# Camera.net
KiCad netlist of a schematic drawn in Altium Designer
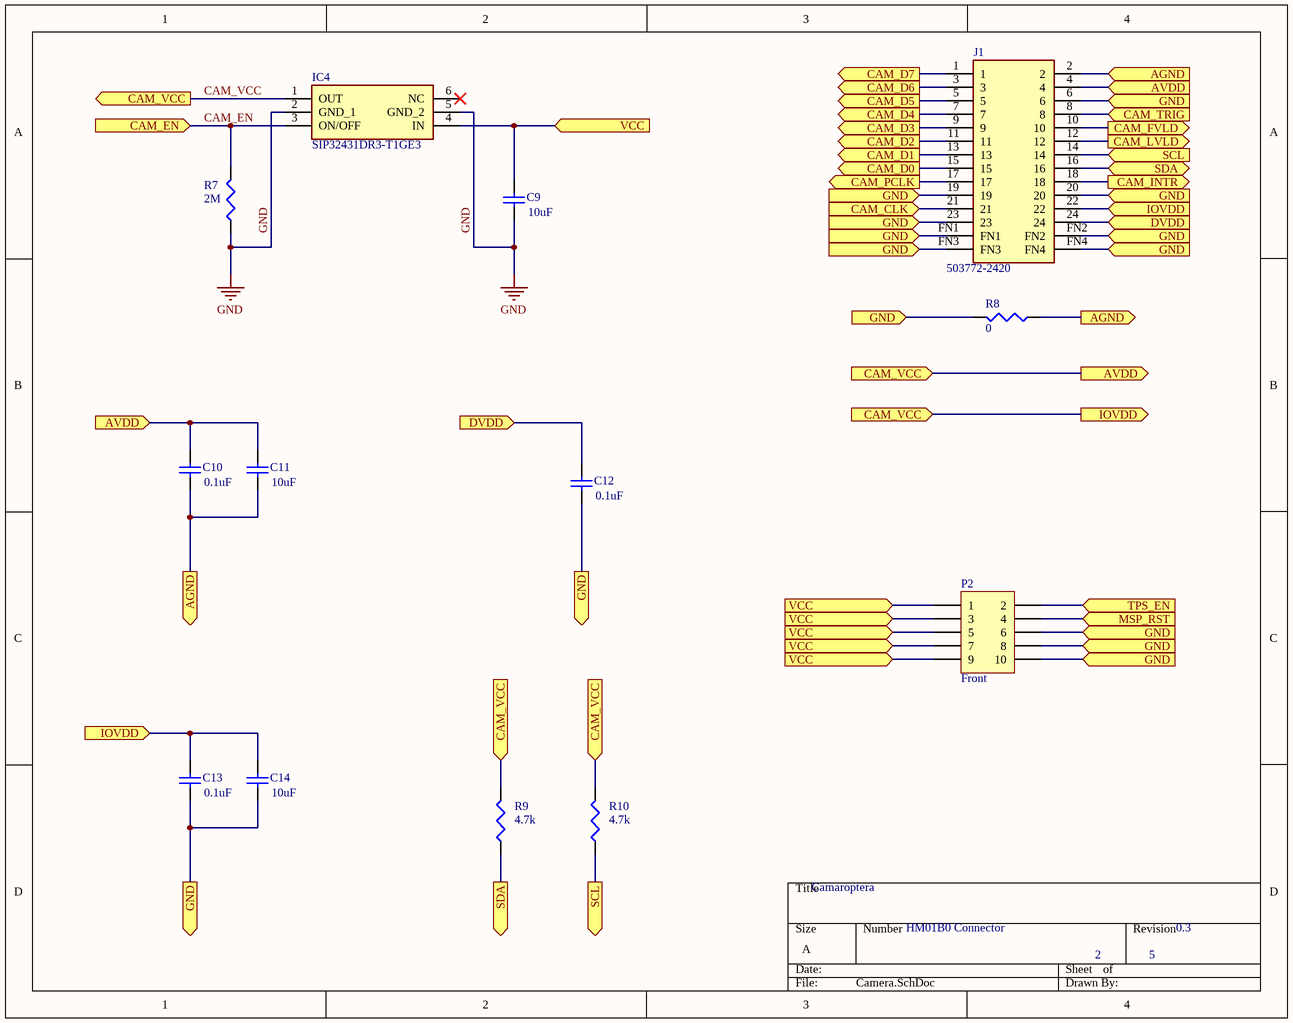
[diagram p0: Camera.SchDoc]

(export (version "E")
  (design (tool "Eeschema 10.0.6"))
  (components
    (comp (ref "C9")
      (value "10uF")
      (footprint "1608[0603]")
      (description "CAP CER 6.3V X5R/X7R 0603")
      (fields (field (name "Comment") "Cap") (field (name "PUBLISHER") "Altium Limited"))
      (libsource (lib "Miscellaneous Devices") (part "Cap"))
    )
    (comp (ref "C10")
      (value "0.1uF")
      (footprint "1608[0603]")
      (description "CAP CER 6.3V X5R/X7R 0603")
      (fields (field (name "Comment") "Cap") (field (name "PUBLISHER") "Altium Limited"))
      (libsource (lib "Miscellaneous Devices") (part "Cap"))
    )
    (comp (ref "C11")
      (value "10uF")
      (footprint "1608[0603]")
      (description "CAP CER 6.3V X5R/X7R 0603")
      (fields (field (name "Comment") "Cap") (field (name "PUBLISHER") "Altium Limited"))
      (libsource (lib "Miscellaneous Devices") (part "Cap"))
    )
    (comp (ref "C12")
      (value "0.1uF")
      (footprint "1608[0603]")
      (description "CAP CER 6.3V X5R/X7R 0603")
      (fields (field (name "Comment") "Cap") (field (name "PUBLISHER") "Altium Limited"))
      (libsource (lib "Miscellaneous Devices") (part "Cap"))
    )
    (comp (ref "C13")
      (value "0.1uF")
      (footprint "1608[0603]")
      (description "CAP CER 6.3V X5R/X7R 0603")
      (fields (field (name "Comment") "Cap") (field (name "PUBLISHER") "Altium Limited"))
      (libsource (lib "Miscellaneous Devices") (part "Cap"))
    )
    (comp (ref "C14")
      (value "10uF")
      (footprint "1608[0603]")
      (description "CAP CER 6.3V X5R/X7R 0603")
      (fields (field (name "Comment") "Cap") (field (name "PUBLISHER") "Altium Limited"))
      (libsource (lib "Miscellaneous Devices") (part "Cap"))
    )
    (comp (ref "IC4")
      (value "SIP32431DR3-T1GE3")
      (footprint "SamacSys:SOT65P210X110-6N")
      (description "10 pA, Ultra Low Leakage and Quiescent Current,\r\nLoad Switch with Reverse Blocking")
      (fields (field (name "MOUSER PART NUMBER") "781-SIP32431DR3-GE3"))
      (libsource (lib "*") (part "SIP32431DR3-T1GE3"))
    )
    (comp (ref "J1")
      (value "503772-2420")
      (footprint "SamacSys:5037722410")
      (fields
        (field (name "MOUSER PART NUMBER") "538-503772-2410")
        (field (name "MANUFACTURER_PART_NUMBER") "503772-2410")
      )
      (libsource (lib "*") (part "503772-2410"))
    )
    (comp (ref "P2")
      (value "Front")
      (footprint "FTE-105-03-X-DH")
      (description "Front  board connector")
      (fields (field (name "PUBLISHER") "Altium Limited"))
      (libsource (lib "Miscellaneous Connectors") (part "Header 5X2"))
    )
    (comp (ref "R7")
      (value "2M")
      (footprint "J1-0603")
      (description "RES 1/10W 1% 0603 SMD")
      (fields (field (name "Comment") "Res3") (field (name "PUBLISHER") "Altium Limited"))
      (libsource (lib "Miscellaneous Devices") (part "Res3"))
    )
    (comp (ref "R8")
      (value "0")
      (footprint "J1-0603")
      (description "RES 1/10W 1% 0603 SMD")
      (fields (field (name "Comment") "Res3") (field (name "PUBLISHER") "Altium Limited"))
      (libsource (lib "Miscellaneous Devices") (part "Res3"))
    )
    (comp (ref "R9")
      (value "4.7k")
      (footprint "J1-0603")
      (description "RES 1/10W 1% 0603 SMD")
      (fields (field (name "Comment") "Res3") (field (name "PUBLISHER") "Altium Limited"))
      (libsource (lib "Miscellaneous Devices") (part "Res3"))
    )
    (comp (ref "R10")
      (value "4.7k")
      (footprint "J1-0603")
      (description "RES 1/10W 1% 0603 SMD")
      (fields (field (name "Comment") "Res3") (field (name "PUBLISHER") "Altium Limited"))
      (libsource (lib "Miscellaneous Devices") (part "Res3"))
    )
  )
  (nets
    (net (code "1") (name "/AGND") (class "Default")
      (node (ref "C10") (pin "1") (pinfunction "1_1") (pintype "passive"))
      (node (ref "C11") (pin "1") (pinfunction "1_1") (pintype "passive"))
      (node (ref "J1") (pin "2") (pinfunction "2_2") (pintype "passive"))
      (node (ref "R8") (pin "1") (pinfunction "1_1") (pintype "passive"))
    )
    (net (code "2") (name "/CAM_CLK") (class "Default")
      (node (ref "J1") (pin "21") (pinfunction "21_21") (pintype "passive"))
    )
    (net (code "3") (name "/CAM_D0") (class "Default")
      (node (ref "J1") (pin "15") (pinfunction "15_15") (pintype "passive"))
    )
    (net (code "4") (name "/CAM_D1") (class "Default")
      (node (ref "J1") (pin "13") (pinfunction "13_13") (pintype "passive"))
    )
    (net (code "5") (name "/CAM_D2") (class "Default")
      (node (ref "J1") (pin "11") (pinfunction "11_11") (pintype "passive"))
    )
    (net (code "6") (name "/CAM_D3") (class "Default")
      (node (ref "J1") (pin "9") (pinfunction "9_9") (pintype "passive"))
    )
    (net (code "7") (name "/CAM_D4") (class "Default")
      (node (ref "J1") (pin "7") (pinfunction "7_7") (pintype "passive"))
    )
    (net (code "8") (name "/CAM_D5") (class "Default")
      (node (ref "J1") (pin "5") (pinfunction "5_5") (pintype "passive"))
    )
    (net (code "9") (name "/CAM_D6") (class "Default")
      (node (ref "J1") (pin "3") (pinfunction "3_3") (pintype "passive"))
    )
    (net (code "10") (name "/CAM_D7") (class "Default")
      (node (ref "J1") (pin "1") (pinfunction "1_1") (pintype "passive"))
    )
    (net (code "11") (name "/CAM_EN") (class "Default")
      (node (ref "IC4") (pin "3") (pinfunction "ON/OFF_3") (pintype "passive"))
      (node (ref "R7") (pin "2") (pinfunction "2_2") (pintype "passive"))
    )
    (net (code "12") (name "/CAM_FVLD") (class "Default")
      (node (ref "J1") (pin "10") (pinfunction "10_10") (pintype "passive"))
    )
    (net (code "13") (name "/CAM_INTR") (class "Default")
      (node (ref "J1") (pin "18") (pinfunction "18_18") (pintype "passive"))
    )
    (net (code "14") (name "/CAM_LVLD") (class "Default")
      (node (ref "J1") (pin "12") (pinfunction "12_12") (pintype "passive"))
    )
    (net (code "15") (name "/CAM_PCLK") (class "Default")
      (node (ref "J1") (pin "17") (pinfunction "17_17") (pintype "passive"))
    )
    (net (code "16") (name "/CAM_TRIG") (class "Default")
      (node (ref "J1") (pin "8") (pinfunction "8_8") (pintype "passive"))
    )
    (net (code "17") (name "/CAM_VCC") (class "Default")
      (node (ref "C10") (pin "2") (pinfunction "2_2") (pintype "passive"))
      (node (ref "C11") (pin "2") (pinfunction "2_2") (pintype "passive"))
      (node (ref "C13") (pin "2") (pinfunction "2_2") (pintype "passive"))
      (node (ref "C14") (pin "2") (pinfunction "2_2") (pintype "passive"))
      (node (ref "IC4") (pin "1") (pinfunction "OUT_1") (pintype "passive"))
      (node (ref "J1") (pin "22") (pinfunction "22_22") (pintype "passive"))
      (node (ref "J1") (pin "4") (pinfunction "4_4") (pintype "passive"))
      (node (ref "R10") (pin "2") (pinfunction "2_2") (pintype "passive"))
      (node (ref "R9") (pin "2") (pinfunction "2_2") (pintype "passive"))
    )
    (net (code "18") (name "/DVDD") (class "Default")
      (node (ref "C12") (pin "2") (pinfunction "2_2") (pintype "passive"))
      (node (ref "J1") (pin "24") (pinfunction "24_24") (pintype "passive"))
    )
    (net (code "19") (name "/MSP_RST") (class "Default")
      (node (ref "P2") (pin "4") (pinfunction "4_4") (pintype "passive"))
    )
    (net (code "20") (name "/SCL") (class "Default")
      (node (ref "J1") (pin "14") (pinfunction "14_14") (pintype "passive"))
      (node (ref "R10") (pin "1") (pinfunction "1_1") (pintype "passive"))
    )
    (net (code "21") (name "/SDA") (class "Default")
      (node (ref "J1") (pin "16") (pinfunction "16_16") (pintype "passive"))
      (node (ref "R9") (pin "1") (pinfunction "1_1") (pintype "passive"))
    )
    (net (code "22") (name "/TPS_EN") (class "Default")
      (node (ref "P2") (pin "2") (pinfunction "2_2") (pintype "passive"))
    )
    (net (code "23") (name "/VCC") (class "Default")
      (node (ref "C9") (pin "2") (pinfunction "2_2") (pintype "passive"))
      (node (ref "IC4") (pin "4") (pinfunction "IN_4") (pintype "passive"))
      (node (ref "P2") (pin "1") (pinfunction "1_1") (pintype "passive"))
      (node (ref "P2") (pin "3") (pinfunction "3_3") (pintype "passive"))
      (node (ref "P2") (pin "5") (pinfunction "5_5") (pintype "passive"))
      (node (ref "P2") (pin "7") (pinfunction "7_7") (pintype "passive"))
      (node (ref "P2") (pin "9") (pinfunction "9_9") (pintype "passive"))
    )
    (net (code "24") (name "GND") (class "Default")
      (node (ref "C12") (pin "1") (pinfunction "1_1") (pintype "passive"))
      (node (ref "C13") (pin "1") (pinfunction "1_1") (pintype "passive"))
      (node (ref "C14") (pin "1") (pinfunction "1_1") (pintype "passive"))
      (node (ref "C9") (pin "1") (pinfunction "1_1") (pintype "passive"))
      (node (ref "IC4") (pin "2") (pinfunction "GND_1_2") (pintype "passive"))
      (node (ref "IC4") (pin "5") (pinfunction "GND_2_5") (pintype "passive"))
      (node (ref "J1") (pin "19") (pinfunction "19_19") (pintype "passive"))
      (node (ref "J1") (pin "20") (pinfunction "20_20") (pintype "passive"))
      (node (ref "J1") (pin "23") (pinfunction "23_23") (pintype "passive"))
      (node (ref "J1") (pin "6") (pinfunction "6_6") (pintype "passive"))
      (node (ref "J1") (pin "FN1") (pinfunction "FN1_FN1") (pintype "passive"))
      (node (ref "J1") (pin "FN2") (pinfunction "FN2_FN2") (pintype "passive"))
      (node (ref "J1") (pin "FN3") (pinfunction "FN3_FN3") (pintype "passive"))
      (node (ref "J1") (pin "FN4") (pinfunction "FN4_FN4") (pintype "passive"))
      (node (ref "P2") (pin "10") (pinfunction "10_10") (pintype "passive"))
      (node (ref "P2") (pin "6") (pinfunction "6_6") (pintype "passive"))
      (node (ref "P2") (pin "8") (pinfunction "8_8") (pintype "passive"))
      (node (ref "R7") (pin "1") (pinfunction "1_1") (pintype "passive"))
      (node (ref "R8") (pin "2") (pinfunction "2_2") (pintype "passive"))
    )
    (net (code "25") (name "unconnected-(IC4-NC-Pad6)") (class "Default")
      (node (ref "IC4") (pin "6") (pinfunction "NC_6") (pintype "passive+no_connect"))
    )
  )
)
